# Dev.net
KiCad netlist of a schematic drawn in Altium Designer
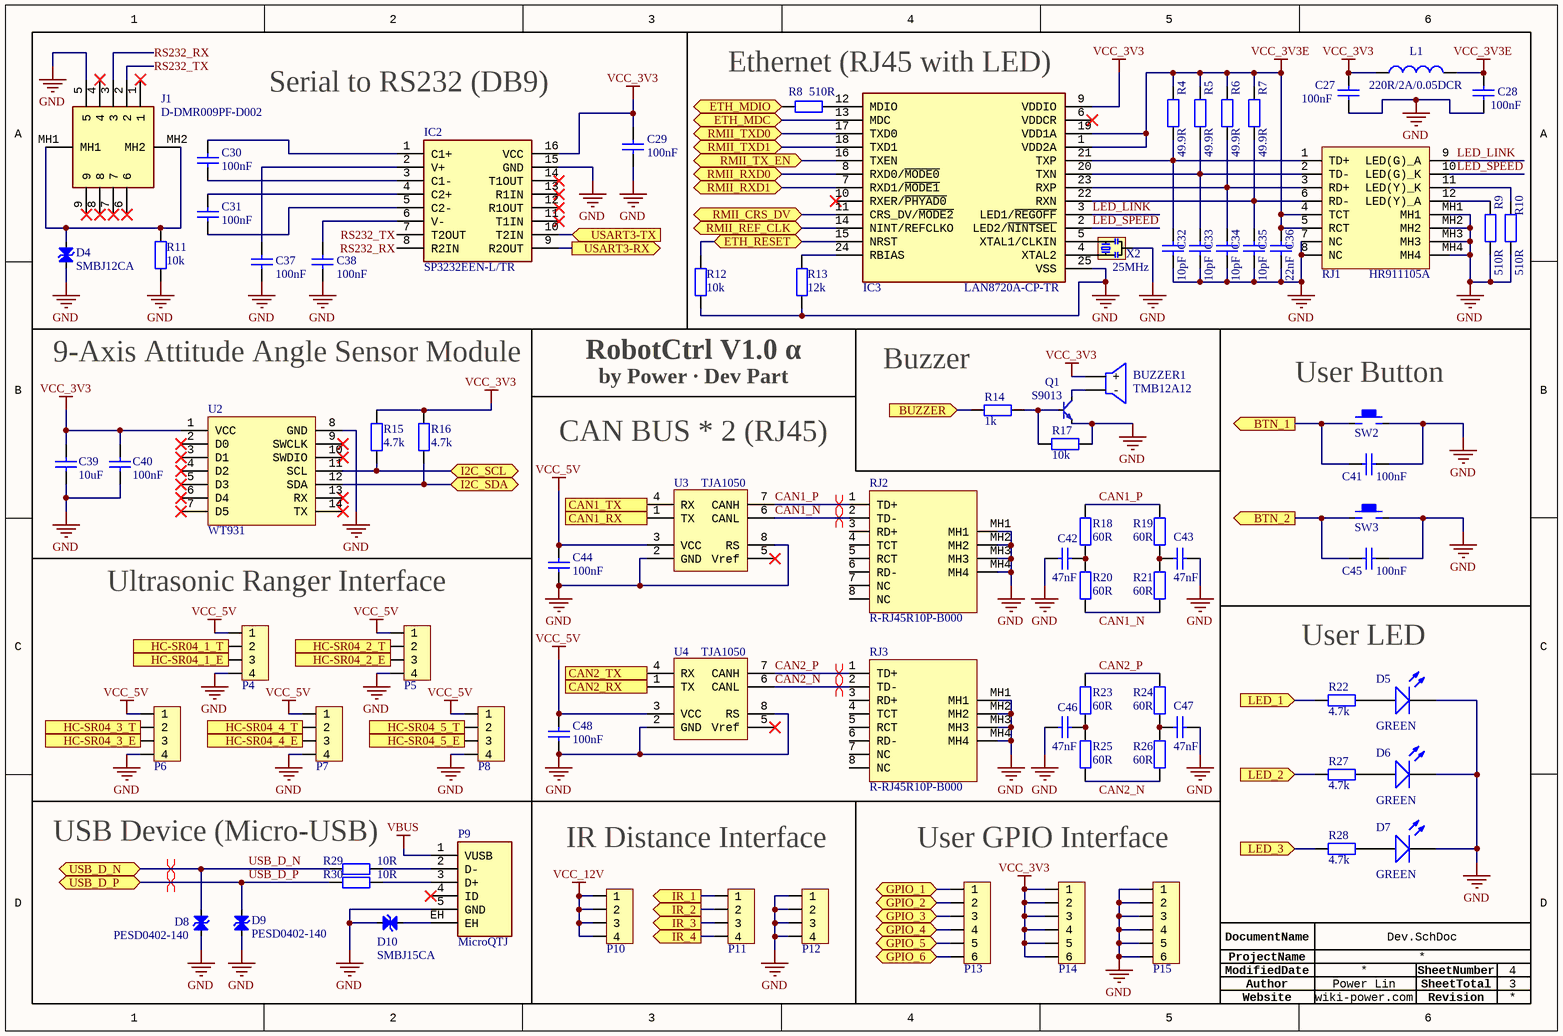
[diagram p0: Dev.SchDoc]

(export (version "E")
  (design (tool "Eeschema 10.0.6"))
  (components
    (comp (ref "BUZZER1")
      (value "TMB12A12")
      (footprint "DIP,P=7.6mm")
      (description "TMB12A12 有源蜂鸣器")
      (libsource (lib "Power_Lib_Altium") (part "BUZZER"))
    )
    (comp (ref "C27")
      (value "100nF")
      (footprint "CAP-0603")
      (description "贴片电容")
      (libsource (lib "Power_Lib_Altium") (part "CAP"))
    )
    (comp (ref "C28")
      (value "100nF")
      (footprint "CAP-0603")
      (description "贴片电容")
      (libsource (lib "Power_Lib_Altium") (part "CAP"))
    )
    (comp (ref "C29")
      (value "100nF")
      (footprint "CAP-0603")
      (description "贴片电容")
      (libsource (lib "Power_Lib_Altium") (part "CAP"))
    )
    (comp (ref "C30")
      (value "100nF")
      (footprint "CAP-0603")
      (description "贴片电容")
      (libsource (lib "Power_Lib_Altium") (part "CAP"))
    )
    (comp (ref "C31")
      (value "100nF")
      (footprint "CAP-0603")
      (description "贴片电容")
      (libsource (lib "Power_Lib_Altium") (part "CAP"))
    )
    (comp (ref "C32")
      (value "10pF")
      (footprint "CAP-0603")
      (description "贴片电容")
      (libsource (lib "Power_Lib_Altium") (part "CAP"))
    )
    (comp (ref "C33")
      (value "10pF")
      (footprint "CAP-0603")
      (description "贴片电容")
      (libsource (lib "Power_Lib_Altium") (part "CAP"))
    )
    (comp (ref "C34")
      (value "10pF")
      (footprint "CAP-0603")
      (description "贴片电容")
      (libsource (lib "Power_Lib_Altium") (part "CAP"))
    )
    (comp (ref "C35")
      (value "10pF")
      (footprint "CAP-0603")
      (description "贴片电容")
      (libsource (lib "Power_Lib_Altium") (part "CAP"))
    )
    (comp (ref "C36")
      (value "22nF")
      (footprint "CAP-0603")
      (description "贴片电容")
      (libsource (lib "Power_Lib_Altium") (part "CAP"))
    )
    (comp (ref "C37")
      (value "100nF")
      (footprint "CAP-0603")
      (description "贴片电容")
      (libsource (lib "Power_Lib_Altium") (part "CAP"))
    )
    (comp (ref "C38")
      (value "100nF")
      (footprint "CAP-0603")
      (description "贴片电容")
      (libsource (lib "Power_Lib_Altium") (part "CAP"))
    )
    (comp (ref "C39")
      (value "10uF")
      (footprint "CAP-0603")
      (description "贴片电容")
      (libsource (lib "Power_Lib_Altium") (part "CAP"))
    )
    (comp (ref "C40")
      (value "100nF")
      (footprint "CAP-0603")
      (description "贴片电容")
      (libsource (lib "Power_Lib_Altium") (part "CAP"))
    )
    (comp (ref "C41")
      (value "100nF")
      (footprint "CAP-0603")
      (description "贴片电容")
      (libsource (lib "Power_Lib_Altium") (part "CAP"))
    )
    (comp (ref "C42")
      (value "47nF")
      (footprint "CAP-0603")
      (description "贴片电容")
      (libsource (lib "Power_Lib_Altium") (part "CAP"))
    )
    (comp (ref "C43")
      (value "47nF")
      (footprint "CAP-0603")
      (description "贴片电容")
      (libsource (lib "Power_Lib_Altium") (part "CAP"))
    )
    (comp (ref "C44")
      (value "100nF")
      (footprint "CAP-0603")
      (description "贴片电容")
      (libsource (lib "Power_Lib_Altium") (part "CAP"))
    )
    (comp (ref "C45")
      (value "100nF")
      (footprint "CAP-0603")
      (description "贴片电容")
      (libsource (lib "Power_Lib_Altium") (part "CAP"))
    )
    (comp (ref "C46")
      (value "47nF")
      (footprint "CAP-0603")
      (description "贴片电容")
      (libsource (lib "Power_Lib_Altium") (part "CAP"))
    )
    (comp (ref "C47")
      (value "47nF")
      (footprint "CAP-0603")
      (description "贴片电容")
      (libsource (lib "Power_Lib_Altium") (part "CAP"))
    )
    (comp (ref "C48")
      (value "100nF")
      (footprint "CAP-0603")
      (description "贴片电容")
      (libsource (lib "Power_Lib_Altium") (part "CAP"))
    )
    (comp (ref "D4")
      (value "SMBJ12CA")
      (footprint "DO-214AA/SMB")
      (libsource (lib "Power_Lib_Altium") (part "TVS_C"))
    )
    (comp (ref "D5")
      (value "GREEN")
      (footprint "LED-0603")
      (description "发光二极管")
      (libsource (lib "Power_Lib_Altium") (part "LED"))
    )
    (comp (ref "D6")
      (value "GREEN")
      (footprint "LED-0603")
      (description "发光二极管")
      (libsource (lib "Power_Lib_Altium") (part "LED"))
    )
    (comp (ref "D7")
      (value "GREEN")
      (footprint "LED-0603")
      (description "发光二极管")
      (libsource (lib "Power_Lib_Altium") (part "LED"))
    )
    (comp (ref "D8")
      (value "PESD0402-140")
      (footprint "D-0402")
      (libsource (lib "Power_Lib_Altium") (part "TVS_C"))
    )
    (comp (ref "D9")
      (value "PESD0402-140")
      (footprint "D-0402")
      (libsource (lib "Power_Lib_Altium") (part "TVS_C"))
    )
    (comp (ref "D10")
      (value "SMBJ15CA")
      (footprint "DO-214AA/SMB")
      (libsource (lib "Power_Lib_Altium") (part "TVS_C"))
    )
    (comp (ref "IC2")
      (value "SP3232EEN-L/TR")
      (footprint "SOIC-16_150mil")
      (description "RS232 芯片")
      (fields (field (name "MOUSER PART NUMBER") "701-SP3232EEN-L/TR"))
      (libsource (lib "Power_Lib_Altium") (part "SP3232EEN"))
    )
    (comp (ref "IC3")
      (value "LAN8720A-CP-TR")
      (footprint "QFN-24-4x4")
      (description "Integrated Circuit")
      (fields (field (name "MOUSER PART NUMBER") "886-LAN8720A-CP-TR"))
      (libsource (lib "Power_Lib_Altium") (part "LAN8720A-CP-TR"))
    )
    (comp (ref "J1")
      (value "D-DMR009PF-D002")
      (footprint "Through Hole,P=2.77mm")
      (description "D-Sub 连接器")
      (fields
        (field (name "MANUFACTURER_PART_NUMBER") "5747844-5")
        (field (name "MOUSER PART NUMBER") "571-5747844-5")
      )
      (libsource (lib "Power_Lib_Altium") (part "DB9"))
    )
    (comp (ref "L1")
      (value "220R/2A/0.05DCR")
      (footprint "L-0603")
      (description "BLM18KG221SN1D")
      (libsource (lib "Power_Lib_Altium") (part "BEAD"))
    )
    (comp (ref "P4")
      (value "HDR1x4_2.54")
      (footprint "HDR1x4_2.54_180")
      (description "Header")
      (libsource (lib "Power_Lib_Altium") (part "HDR1x4_2.54"))
    )
    (comp (ref "P5")
      (value "HDR1x4_2.54")
      (footprint "HDR1x4_2.54_180")
      (description "Header")
      (libsource (lib "Power_Lib_Altium") (part "HDR1x4_2.54"))
    )
    (comp (ref "P6")
      (value "HDR1x4_2.54")
      (footprint "HDR1x4_2.54_180")
      (description "Header")
      (libsource (lib "Power_Lib_Altium") (part "HDR1x4_2.54"))
    )
    (comp (ref "P7")
      (value "HDR1x4_2.54")
      (footprint "HDR1x4_2.54_180")
      (description "Header")
      (libsource (lib "Power_Lib_Altium") (part "HDR1x4_2.54"))
    )
    (comp (ref "P8")
      (value "HDR1x4_2.54")
      (footprint "HDR1x4_2.54_180")
      (description "Header")
      (libsource (lib "Power_Lib_Altium") (part "HDR1x4_2.54"))
    )
    (comp (ref "P9")
      (value "MicroQTJ")
      (footprint "USB-MICRO")
      (description "USB_MICRO")
      (libsource (lib "Power_Lib_Altium") (part "USB_MICRO"))
    )
    (comp (ref "P10")
      (value "HDR1x4_2.54")
      (footprint "HDR1x4_2.54_180")
      (description "Header")
      (libsource (lib "Power_Lib_Altium") (part "HDR1x4_2.54"))
    )
    (comp (ref "P11")
      (value "HDR1x4_2.54")
      (footprint "HDR1x4_2.54_180")
      (description "Header")
      (libsource (lib "Power_Lib_Altium") (part "HDR1x4_2.54"))
    )
    (comp (ref "P12")
      (value "HDR1x4_2.54")
      (footprint "HDR1x4_2.54_180")
      (description "Header")
      (libsource (lib "Power_Lib_Altium") (part "HDR1x4_2.54"))
    )
    (comp (ref "P13")
      (value "HDR1x6")
      (footprint "HDR1X6_2.54_180")
      (description "Header")
      (libsource (lib "Power_Lib_Altium") (part "HDR1x6_2.54"))
    )
    (comp (ref "P14")
      (value "HDR1x6")
      (footprint "HDR1X6_2.54_180")
      (description "Header")
      (libsource (lib "Power_Lib_Altium") (part "HDR1x6_2.54"))
    )
    (comp (ref "P15")
      (value "HDR1x6")
      (footprint "HDR1X6_2.54_180")
      (description "Header")
      (libsource (lib "Power_Lib_Altium") (part "HDR1x6_2.54"))
    )
    (comp (ref "Q1")
      (value "S9013")
      (footprint "SOT-23-3")
      (libsource (lib "Power_Lib_Altium") (part "BJT_NPN"))
    )
    (comp (ref "R4")
      (value "49.9R")
      (footprint "R-0603")
      (description "贴片电阻")
      (libsource (lib "Power_Lib_Altium") (part "RES"))
    )
    (comp (ref "R5")
      (value "49.9R")
      (footprint "R-0603")
      (description "贴片电阻")
      (libsource (lib "Power_Lib_Altium") (part "RES"))
    )
    (comp (ref "R6")
      (value "49.9R")
      (footprint "R-0603")
      (description "贴片电阻")
      (libsource (lib "Power_Lib_Altium") (part "RES"))
    )
    (comp (ref "R7")
      (value "49.9R")
      (footprint "R-0603")
      (description "贴片电阻")
      (libsource (lib "Power_Lib_Altium") (part "RES"))
    )
    (comp (ref "R8")
      (value "510R")
      (footprint "R-0603")
      (description "贴片电阻")
      (libsource (lib "") (part "RES_1"))
    )
    (comp (ref "R9")
      (value "510R")
      (footprint "R-0603")
      (description "贴片电阻")
      (libsource (lib "Power_Lib_Altium") (part "RES"))
    )
    (comp (ref "R10")
      (value "510R")
      (footprint "R-0603")
      (description "贴片电阻")
      (libsource (lib "Power_Lib_Altium") (part "RES"))
    )
    (comp (ref "R11")
      (value "10k")
      (footprint "R-0603")
      (description "贴片电阻")
      (libsource (lib "Power_Lib_Altium") (part "RES"))
    )
    (comp (ref "R12")
      (value "10k")
      (footprint "R-0603")
      (description "贴片电阻")
      (libsource (lib "") (part "RES_3"))
    )
    (comp (ref "R13")
      (value "12k")
      (footprint "R-0603")
      (description "贴片电阻")
      (libsource (lib "") (part "RES_3"))
    )
    (comp (ref "R14")
      (value "1k")
      (footprint "R-0603")
      (description "贴片电阻")
      (libsource (lib "") (part "RES_2"))
    )
    (comp (ref "R15")
      (value "4.7k")
      (footprint "R-0603")
      (description "贴片电阻")
      (libsource (lib "Power_Lib_Altium") (part "RES"))
    )
    (comp (ref "R16")
      (value "4.7k")
      (footprint "R-0603")
      (description "贴片电阻")
      (libsource (lib "Power_Lib_Altium") (part "RES"))
    )
    (comp (ref "R17")
      (value "10k")
      (footprint "R-0603")
      (description "贴片电阻")
      (libsource (lib "") (part "RES_1"))
    )
    (comp (ref "R18")
      (value "60R")
      (footprint "R-0603")
      (description "贴片电阻")
      (libsource (lib "") (part "RES_3"))
    )
    (comp (ref "R19")
      (value "60R")
      (footprint "R-0603")
      (description "贴片电阻")
      (libsource (lib "Power_Lib_Altium") (part "RES"))
    )
    (comp (ref "R20")
      (value "60R")
      (footprint "R-0603")
      (description "贴片电阻")
      (libsource (lib "") (part "RES_3"))
    )
    (comp (ref "R21")
      (value "60R")
      (footprint "R-0603")
      (description "贴片电阻")
      (libsource (lib "Power_Lib_Altium") (part "RES"))
    )
    (comp (ref "R22")
      (value "4.7k")
      (footprint "R-0603")
      (description "贴片电阻")
      (libsource (lib "") (part "RES_1"))
    )
    (comp (ref "R23")
      (value "60R")
      (footprint "R-0603")
      (description "贴片电阻")
      (libsource (lib "") (part "RES_3"))
    )
    (comp (ref "R24")
      (value "60R")
      (footprint "R-0603")
      (description "贴片电阻")
      (libsource (lib "Power_Lib_Altium") (part "RES"))
    )
    (comp (ref "R25")
      (value "60R")
      (footprint "R-0603")
      (description "贴片电阻")
      (libsource (lib "") (part "RES_3"))
    )
    (comp (ref "R26")
      (value "60R")
      (footprint "R-0603")
      (description "贴片电阻")
      (libsource (lib "Power_Lib_Altium") (part "RES"))
    )
    (comp (ref "R27")
      (value "4.7k")
      (footprint "R-0603")
      (description "贴片电阻")
      (libsource (lib "") (part "RES_1"))
    )
    (comp (ref "R28")
      (value "4.7k")
      (footprint "R-0603")
      (description "贴片电阻")
      (libsource (lib "") (part "RES_1"))
    )
    (comp (ref "R29")
      (value "10R")
      (footprint "R-0603")
      (description "贴片电阻")
      (libsource (lib "") (part "RES_2"))
    )
    (comp (ref "R30")
      (value "10R")
      (footprint "R-0603")
      (description "贴片电阻")
      (libsource (lib "") (part "RES_2"))
    )
    (comp (ref "RJ1")
      (value "HR911105A")
      (footprint "HR911105A")
      (libsource (lib "Power_Lib_Altium") (part "RJ45_LED"))
    )
    (comp (ref "RJ2")
      (value "R-RJ45R10P-B000")
      (footprint "RRJ45R10PB000")
      (libsource (lib "Power_Lib_Altium") (part "RJ45"))
    )
    (comp (ref "RJ3")
      (value "R-RJ45R10P-B000")
      (footprint "RRJ45R10PB000")
      (libsource (lib "Power_Lib_Altium") (part "RJ45"))
    )
    (comp (ref "SW2")
      (value "KEY")
      (footprint "KEY-4P-4.2*3.4*2.5")
      (description "按键开关")
      (libsource (lib "Power_Lib_Altium") (part "KEY"))
    )
    (comp (ref "SW3")
      (value "KEY")
      (footprint "KEY-4P-4.2*3.4*2.5")
      (description "按键开关")
      (libsource (lib "Power_Lib_Altium") (part "KEY"))
    )
    (comp (ref "U2")
      (value "WT931")
      (footprint "WT931")
      (description "陀螺仪模组")
      (libsource (lib "Power_Lib_Altium") (part "WT931"))
    )
    (comp (ref "U3")
      (value "TJA1050")
      (footprint "SOIC_8")
      (description "CAN 控制器（5V）")
      (libsource (lib "Power_Lib_Altium") (part "TJA1050"))
    )
    (comp (ref "U4")
      (value "TJA1050")
      (footprint "SOIC_8")
      (description "CAN 控制器（5V）")
      (libsource (lib "Power_Lib_Altium") (part "TJA1050"))
    )
    (comp (ref "X2")
      (value "25MHz")
      (footprint "SMD3213-3P")
      (description "CSTCE25M00G51-R0")
      (libsource (lib "Power_Lib_Altium") (part "XTAL"))
    )
  )
  (nets
    (net (code "1") (name "/BTN_1") (class "Default")
      (node (ref "C41") (pin "2") (pinfunction "2_2") (pintype "passive"))
      (node (ref "SW2") (pin "1") (pinfunction "1_1") (pintype "passive"))
    )
    (net (code "2") (name "/BTN_2") (class "Default")
      (node (ref "C45") (pin "2") (pinfunction "2_2") (pintype "passive"))
      (node (ref "SW3") (pin "1") (pinfunction "1_1") (pintype "passive"))
    )
    (net (code "3") (name "/BUZZER") (class "Default")
      (node (ref "R14") (pin "1") (pinfunction "1_1") (pintype "passive"))
    )
    (net (code "4") (name "/CAN1_N") (class "Default")
      (node (ref "R20") (pin "2") (pinfunction "2_2") (pintype "passive"))
      (node (ref "R21") (pin "1") (pinfunction "1_1") (pintype "passive"))
      (node (ref "RJ2") (pin "2") (pinfunction "TD-_2") (pintype "passive"))
      (node (ref "U3") (pin "6") (pinfunction "CANL_6") (pintype "passive"))
    )
    (net (code "5") (name "/CAN1_P") (class "Default")
      (node (ref "R18") (pin "1") (pinfunction "1_1") (pintype "passive"))
      (node (ref "R19") (pin "2") (pinfunction "2_2") (pintype "passive"))
      (node (ref "RJ2") (pin "1") (pinfunction "TD+_1") (pintype "passive"))
      (node (ref "U3") (pin "7") (pinfunction "CANH_7") (pintype "passive"))
    )
    (net (code "6") (name "/CAN1_RX") (class "Default")
      (node (ref "U3") (pin "1") (pinfunction "TX_1") (pintype "passive"))
    )
    (net (code "7") (name "/CAN1_TX") (class "Default")
      (node (ref "U3") (pin "4") (pinfunction "RX_4") (pintype "passive"))
    )
    (net (code "8") (name "/CAN2_N") (class "Default")
      (node (ref "R25") (pin "2") (pinfunction "2_2") (pintype "passive"))
      (node (ref "R26") (pin "1") (pinfunction "1_1") (pintype "passive"))
      (node (ref "RJ3") (pin "2") (pinfunction "TD-_2") (pintype "passive"))
      (node (ref "U4") (pin "6") (pinfunction "CANL_6") (pintype "passive"))
    )
    (net (code "9") (name "/CAN2_P") (class "Default")
      (node (ref "R23") (pin "1") (pinfunction "1_1") (pintype "passive"))
      (node (ref "R24") (pin "2") (pinfunction "2_2") (pintype "passive"))
      (node (ref "RJ3") (pin "1") (pinfunction "TD+_1") (pintype "passive"))
      (node (ref "U4") (pin "7") (pinfunction "CANH_7") (pintype "passive"))
    )
    (net (code "10") (name "/CAN2_RX") (class "Default")
      (node (ref "U4") (pin "1") (pinfunction "TX_1") (pintype "passive"))
    )
    (net (code "11") (name "/CAN2_TX") (class "Default")
      (node (ref "U4") (pin "4") (pinfunction "RX_4") (pintype "passive"))
    )
    (net (code "12") (name "/ETH_MDC") (class "Default")
      (node (ref "IC3") (pin "13") (pinfunction "MDC_13") (pintype "passive"))
    )
    (net (code "13") (name "/ETH_MDIO") (class "Default")
      (node (ref "R8") (pin "2") (pinfunction "2_2") (pintype "passive"))
    )
    (net (code "14") (name "/ETH_RESET") (class "Default")
      (node (ref "IC3") (pin "15") (pinfunction "NRST_15") (pintype "passive"))
      (node (ref "R12") (pin "1") (pinfunction "1_1") (pintype "passive"))
    )
    (net (code "15") (name "/GPIO_1") (class "Default")
      (node (ref "P13") (pin "1") (pinfunction "1_1") (pintype "passive"))
    )
    (net (code "16") (name "/GPIO_2") (class "Default")
      (node (ref "P13") (pin "2") (pinfunction "2_2") (pintype "passive"))
    )
    (net (code "17") (name "/GPIO_3") (class "Default")
      (node (ref "P13") (pin "3") (pinfunction "3_3") (pintype "passive"))
    )
    (net (code "18") (name "/GPIO_4") (class "Default")
      (node (ref "P13") (pin "4") (pinfunction "4_4") (pintype "passive"))
    )
    (net (code "19") (name "/GPIO_5") (class "Default")
      (node (ref "P13") (pin "5") (pinfunction "5_5") (pintype "passive"))
    )
    (net (code "20") (name "/GPIO_6") (class "Default")
      (node (ref "P13") (pin "6") (pinfunction "6_6") (pintype "passive"))
    )
    (net (code "21") (name "/HC-SR04_1_E") (class "Default")
      (node (ref "P4") (pin "3") (pinfunction "3_3") (pintype "passive"))
    )
    (net (code "22") (name "/HC-SR04_1_T") (class "Default")
      (node (ref "P4") (pin "2") (pinfunction "2_2") (pintype "passive"))
    )
    (net (code "23") (name "/HC-SR04_2_E") (class "Default")
      (node (ref "P5") (pin "3") (pinfunction "3_3") (pintype "passive"))
    )
    (net (code "24") (name "/HC-SR04_2_T") (class "Default")
      (node (ref "P5") (pin "2") (pinfunction "2_2") (pintype "passive"))
    )
    (net (code "25") (name "/HC-SR04_3_E") (class "Default")
      (node (ref "P6") (pin "3") (pinfunction "3_3") (pintype "passive"))
    )
    (net (code "26") (name "/HC-SR04_3_T") (class "Default")
      (node (ref "P6") (pin "2") (pinfunction "2_2") (pintype "passive"))
    )
    (net (code "27") (name "/HC-SR04_4_E") (class "Default")
      (node (ref "P7") (pin "3") (pinfunction "3_3") (pintype "passive"))
    )
    (net (code "28") (name "/HC-SR04_4_T") (class "Default")
      (node (ref "P7") (pin "2") (pinfunction "2_2") (pintype "passive"))
    )
    (net (code "29") (name "/HC-SR04_5_E") (class "Default")
      (node (ref "P8") (pin "3") (pinfunction "3_3") (pintype "passive"))
    )
    (net (code "30") (name "/HC-SR04_5_T") (class "Default")
      (node (ref "P8") (pin "2") (pinfunction "2_2") (pintype "passive"))
    )
    (net (code "31") (name "/I2C_SCL") (class "Default")
      (node (ref "R15") (pin "1") (pinfunction "1_1") (pintype "passive"))
      (node (ref "U2") (pin "11") (pinfunction "SCL_11") (pintype "passive"))
    )
    (net (code "32") (name "/I2C_SDA") (class "Default")
      (node (ref "R16") (pin "1") (pinfunction "1_1") (pintype "passive"))
      (node (ref "U2") (pin "12") (pinfunction "SDA_12") (pintype "passive"))
    )
    (net (code "33") (name "/IR_1") (class "Default")
      (node (ref "P11") (pin "1") (pinfunction "1_1") (pintype "passive"))
    )
    (net (code "34") (name "/IR_2") (class "Default")
      (node (ref "P11") (pin "2") (pinfunction "2_2") (pintype "passive"))
    )
    (net (code "35") (name "/IR_3") (class "Default")
      (node (ref "P11") (pin "3") (pinfunction "3_3") (pintype "passive"))
    )
    (net (code "36") (name "/IR_4") (class "Default")
      (node (ref "P11") (pin "4") (pinfunction "4_4") (pintype "passive"))
    )
    (net (code "37") (name "/LED_1") (class "Default")
      (node (ref "R22") (pin "2") (pinfunction "2_2") (pintype "passive"))
    )
    (net (code "38") (name "/LED_2") (class "Default")
      (node (ref "R27") (pin "2") (pinfunction "2_2") (pintype "passive"))
    )
    (net (code "39") (name "/LED_3") (class "Default")
      (node (ref "R28") (pin "2") (pinfunction "2_2") (pintype "passive"))
    )
    (net (code "40") (name "/LED_LINK") (class "Default")
      (node (ref "IC3") (pin "3") (pinfunction "LED1/~{REGOFF}_3") (pintype "passive"))
      (node (ref "RJ1") (pin "9") (pinfunction "LED(G)_A_9") (pintype "passive"))
    )
    (net (code "41") (name "/LED_SPEED") (class "Default")
      (node (ref "IC3") (pin "2") (pinfunction "LED2/~{NINTSEL}_2") (pintype "passive"))
      (node (ref "RJ1") (pin "10") (pinfunction "LED(G)_K_10") (pintype "passive"))
    )
    (net (code "42") (name "/RMII_CRS_DV") (class "Default")
      (node (ref "IC3") (pin "11") (pinfunction "CRS_DV/~{MODE2}_11") (pintype "passive"))
    )
    (net (code "43") (name "/RMII_REF_CLK") (class "Default")
      (node (ref "IC3") (pin "14") (pinfunction "NINT/REFCLKO_14") (pintype "passive"))
    )
    (net (code "44") (name "/RMII_RXD0") (class "Default")
      (node (ref "IC3") (pin "8") (pinfunction "RXD0/~{MODE0}_8") (pintype "passive"))
    )
    (net (code "45") (name "/RMII_RXD1") (class "Default")
      (node (ref "IC3") (pin "7") (pinfunction "RXD1/~{MODE1}_7") (pintype "passive"))
    )
    (net (code "46") (name "/RMII_TXD0") (class "Default")
      (node (ref "IC3") (pin "17") (pinfunction "TXD0_17") (pintype "passive"))
    )
    (net (code "47") (name "/RMII_TXD1") (class "Default")
      (node (ref "IC3") (pin "18") (pinfunction "TXD1_18") (pintype "passive"))
    )
    (net (code "48") (name "/RMII_TX_EN") (class "Default")
      (node (ref "IC3") (pin "16") (pinfunction "TXEN_16") (pintype "passive"))
    )
    (net (code "49") (name "/RS232_RX") (class "Default")
      (node (ref "IC2") (pin "8") (pinfunction "R2IN_8") (pintype "passive"))
      (node (ref "J1") (pin "3") (pinfunction "3_3") (pintype "passive"))
    )
    (net (code "50") (name "/RS232_TX") (class "Default")
      (node (ref "IC2") (pin "7") (pinfunction "T2OUT_7") (pintype "passive"))
      (node (ref "J1") (pin "2") (pinfunction "2_2") (pintype "passive"))
    )
    (net (code "51") (name "/USART3-RX") (class "Default")
      (node (ref "IC2") (pin "9") (pinfunction "R2OUT_9") (pintype "passive"))
    )
    (net (code "52") (name "/USART3-TX") (class "Default")
      (node (ref "IC2") (pin "10") (pinfunction "T2IN_10") (pintype "passive"))
    )
    (net (code "53") (name "/USB_D_N") (class "Default")
      (node (ref "D8") (pin "2") (pinfunction "2_2") (pintype "passive"))
      (node (ref "R29") (pin "1") (pinfunction "1_1") (pintype "passive"))
    )
    (net (code "54") (name "/USB_D_P") (class "Default")
      (node (ref "D9") (pin "2") (pinfunction "2_2") (pintype "passive"))
      (node (ref "R30") (pin "1") (pinfunction "1_1") (pintype "passive"))
    )
    (net (code "55") (name "GND") (class "Default")
      (node (ref "C27") (pin "1") (pinfunction "1_1") (pintype "passive"))
      (node (ref "C28") (pin "1") (pinfunction "1_1") (pintype "passive"))
      (node (ref "C29") (pin "1") (pinfunction "1_1") (pintype "passive"))
      (node (ref "C32") (pin "1") (pinfunction "1_1") (pintype "passive"))
      (node (ref "C33") (pin "1") (pinfunction "1_1") (pintype "passive"))
      (node (ref "C34") (pin "1") (pinfunction "1_1") (pintype "passive"))
      (node (ref "C35") (pin "1") (pinfunction "1_1") (pintype "passive"))
      (node (ref "C36") (pin "1") (pinfunction "1_1") (pintype "passive"))
      (node (ref "C37") (pin "1") (pinfunction "1_1") (pintype "passive"))
      (node (ref "C38") (pin "1") (pinfunction "1_1") (pintype "passive"))
      (node (ref "C39") (pin "2") (pinfunction "2_2") (pintype "passive"))
      (node (ref "C40") (pin "2") (pinfunction "2_2") (pintype "passive"))
      (node (ref "C41") (pin "1") (pinfunction "1_1") (pintype "passive"))
      (node (ref "C42") (pin "2") (pinfunction "2_2") (pintype "passive"))
      (node (ref "C43") (pin "2") (pinfunction "2_2") (pintype "passive"))
      (node (ref "C44") (pin "1") (pinfunction "1_1") (pintype "passive"))
      (node (ref "C45") (pin "1") (pinfunction "1_1") (pintype "passive"))
      (node (ref "C46") (pin "2") (pinfunction "2_2") (pintype "passive"))
      (node (ref "C47") (pin "2") (pinfunction "2_2") (pintype "passive"))
      (node (ref "C48") (pin "1") (pinfunction "1_1") (pintype "passive"))
      (node (ref "D10") (pin "2") (pinfunction "2_2") (pintype "passive"))
      (node (ref "D4") (pin "1") (pinfunction "1_1") (pintype "passive"))
      (node (ref "D5") (pin "K") (pinfunction "K_K") (pintype "passive"))
      (node (ref "D6") (pin "K") (pinfunction "K_K") (pintype "passive"))
      (node (ref "D7") (pin "K") (pinfunction "K_K") (pintype "passive"))
      (node (ref "D8") (pin "1") (pinfunction "1_1") (pintype "passive"))
      (node (ref "D9") (pin "1") (pinfunction "1_1") (pintype "passive"))
      (node (ref "IC2") (pin "15") (pinfunction "GND_15") (pintype "passive"))
      (node (ref "IC3") (pin "25") (pinfunction "VSS_25") (pintype "passive"))
      (node (ref "J1") (pin "5") (pinfunction "5_5") (pintype "passive"))
      (node (ref "P12") (pin "1") (pinfunction "1_1") (pintype "passive"))
      (node (ref "P12") (pin "2") (pinfunction "2_2") (pintype "passive"))
      (node (ref "P12") (pin "3") (pinfunction "3_3") (pintype "passive"))
      (node (ref "P12") (pin "4") (pinfunction "4_4") (pintype "passive"))
      (node (ref "P15") (pin "1") (pinfunction "1_1") (pintype "passive"))
      (node (ref "P15") (pin "2") (pinfunction "2_2") (pintype "passive"))
      (node (ref "P15") (pin "3") (pinfunction "3_3") (pintype "passive"))
      (node (ref "P15") (pin "4") (pinfunction "4_4") (pintype "passive"))
      (node (ref "P15") (pin "5") (pinfunction "5_5") (pintype "passive"))
      (node (ref "P15") (pin "6") (pinfunction "6_6") (pintype "passive"))
      (node (ref "P4") (pin "4") (pinfunction "4_4") (pintype "passive"))
      (node (ref "P5") (pin "4") (pinfunction "4_4") (pintype "passive"))
      (node (ref "P6") (pin "4") (pinfunction "4_4") (pintype "passive"))
      (node (ref "P7") (pin "4") (pinfunction "4_4") (pintype "passive"))
      (node (ref "P8") (pin "4") (pinfunction "4_4") (pintype "passive"))
      (node (ref "P9") (pin "5") (pinfunction "GND_5") (pintype "passive"))
      (node (ref "Q1") (pin "2") (pinfunction "E_2") (pintype "passive"))
      (node (ref "R10") (pin "1") (pinfunction "1_1") (pintype "passive"))
      (node (ref "R11") (pin "1") (pinfunction "1_1") (pintype "passive"))
      (node (ref "R12") (pin "2") (pinfunction "2_2") (pintype "passive"))
      (node (ref "R13") (pin "2") (pinfunction "2_2") (pintype "passive"))
      (node (ref "R17") (pin "1") (pinfunction "1_1") (pintype "passive"))
      (node (ref "R9") (pin "1") (pinfunction "1_1") (pintype "passive"))
      (node (ref "RJ1") (pin "7") (pinfunction "NC_7") (pintype "passive"))
      (node (ref "RJ1") (pin "8") (pinfunction "NC_8") (pintype "passive"))
      (node (ref "RJ1") (pin "MH1") (pinfunction "MH1_MH1") (pintype "passive"))
      (node (ref "RJ1") (pin "MH2") (pinfunction "MH2_MH2") (pintype "passive"))
      (node (ref "RJ1") (pin "MH3") (pinfunction "MH3_MH3") (pintype "passive"))
      (node (ref "RJ1") (pin "MH4") (pinfunction "MH4_MH4") (pintype "passive"))
      (node (ref "RJ2") (pin "MH1") (pinfunction "MH1_MH1") (pintype "passive"))
      (node (ref "RJ2") (pin "MH2") (pinfunction "MH2_MH2") (pintype "passive"))
      (node (ref "RJ2") (pin "MH3") (pinfunction "MH3_MH3") (pintype "passive"))
      (node (ref "RJ2") (pin "MH4") (pinfunction "MH4_MH4") (pintype "passive"))
      (node (ref "RJ3") (pin "MH1") (pinfunction "MH1_MH1") (pintype "passive"))
      (node (ref "RJ3") (pin "MH2") (pinfunction "MH2_MH2") (pintype "passive"))
      (node (ref "RJ3") (pin "MH3") (pinfunction "MH3_MH3") (pintype "passive"))
      (node (ref "RJ3") (pin "MH4") (pinfunction "MH4_MH4") (pintype "passive"))
      (node (ref "SW2") (pin "2") (pinfunction "2_2") (pintype "passive"))
      (node (ref "SW3") (pin "2") (pinfunction "2_2") (pintype "passive"))
      (node (ref "U2") (pin "8") (pinfunction "GND_8") (pintype "passive"))
      (node (ref "U3") (pin "2") (pinfunction "GND_2") (pintype "passive"))
      (node (ref "U3") (pin "8") (pinfunction "RS_8") (pintype "passive"))
      (node (ref "U4") (pin "2") (pinfunction "GND_2") (pintype "passive"))
      (node (ref "U4") (pin "8") (pinfunction "RS_8") (pintype "passive"))
      (node (ref "X2") (pin "2") (pinfunction "GND_2") (pintype "passive"))
    )
    (net (code "56") (name "Net-(BUZZER1--)") (class "Default")
      (node (ref "BUZZER1") (pin "2") (pinfunction "-_2") (pintype "passive"))
      (node (ref "Q1") (pin "3") (pinfunction "C_3") (pintype "passive"))
    )
    (net (code "57") (name "Net-(C42-Pad1)") (class "Default")
      (node (ref "C42") (pin "1") (pinfunction "1_1") (pintype "passive"))
      (node (ref "R18") (pin "2") (pinfunction "2_2") (pintype "passive"))
      (node (ref "R20") (pin "1") (pinfunction "1_1") (pintype "passive"))
    )
    (net (code "58") (name "Net-(C43-Pad1)") (class "Default")
      (node (ref "C43") (pin "1") (pinfunction "1_1") (pintype "passive"))
      (node (ref "R19") (pin "1") (pinfunction "1_1") (pintype "passive"))
      (node (ref "R21") (pin "2") (pinfunction "2_2") (pintype "passive"))
    )
    (net (code "59") (name "Net-(C46-Pad1)") (class "Default")
      (node (ref "C46") (pin "1") (pinfunction "1_1") (pintype "passive"))
      (node (ref "R23") (pin "2") (pinfunction "2_2") (pintype "passive"))
      (node (ref "R25") (pin "1") (pinfunction "1_1") (pintype "passive"))
    )
    (net (code "60") (name "Net-(C47-Pad1)") (class "Default")
      (node (ref "C47") (pin "1") (pinfunction "1_1") (pintype "passive"))
      (node (ref "R24") (pin "1") (pinfunction "1_1") (pintype "passive"))
      (node (ref "R26") (pin "2") (pinfunction "2_2") (pintype "passive"))
    )
    (net (code "61") (name "Net-(D4-Pad2)") (class "Default")
      (node (ref "D4") (pin "2") (pinfunction "2_2") (pintype "passive"))
      (node (ref "J1") (pin "MH1") (pinfunction "MH1_MH1") (pintype "passive"))
      (node (ref "J1") (pin "MH2") (pinfunction "MH2_MH2") (pintype "passive"))
      (node (ref "R11") (pin "2") (pinfunction "2_2") (pintype "passive"))
    )
    (net (code "62") (name "Net-(D5-PadA)") (class "Default")
      (node (ref "D5") (pin "A") (pinfunction "A_A") (pintype "passive"))
      (node (ref "R22") (pin "1") (pinfunction "1_1") (pintype "passive"))
    )
    (net (code "63") (name "Net-(D6-PadA)") (class "Default")
      (node (ref "D6") (pin "A") (pinfunction "A_A") (pintype "passive"))
      (node (ref "R27") (pin "1") (pinfunction "1_1") (pintype "passive"))
    )
    (net (code "64") (name "Net-(D7-PadA)") (class "Default")
      (node (ref "D7") (pin "A") (pinfunction "A_A") (pintype "passive"))
      (node (ref "R28") (pin "1") (pinfunction "1_1") (pintype "passive"))
    )
    (net (code "65") (name "Net-(D10-Pad1)") (class "Default")
      (node (ref "D10") (pin "1") (pinfunction "1_1") (pintype "passive"))
      (node (ref "P9") (pin "EH") (pinfunction "EH_EH") (pintype "passive"))
    )
    (net (code "66") (name "Net-(IC2-C1+)") (class "Default")
      (node (ref "C30") (pin "2") (pinfunction "2_2") (pintype "passive"))
      (node (ref "IC2") (pin "1") (pinfunction "C1+_1") (pintype "passive"))
    )
    (net (code "67") (name "Net-(IC2-C1-)") (class "Default")
      (node (ref "C30") (pin "1") (pinfunction "1_1") (pintype "passive"))
      (node (ref "IC2") (pin "3") (pinfunction "C1-_3") (pintype "passive"))
    )
    (net (code "68") (name "Net-(IC2-C2+)") (class "Default")
      (node (ref "C31") (pin "2") (pinfunction "2_2") (pintype "passive"))
      (node (ref "IC2") (pin "4") (pinfunction "C2+_4") (pintype "passive"))
    )
    (net (code "69") (name "Net-(IC2-C2-)") (class "Default")
      (node (ref "C31") (pin "1") (pinfunction "1_1") (pintype "passive"))
      (node (ref "IC2") (pin "5") (pinfunction "C2-_5") (pintype "passive"))
    )
    (net (code "70") (name "Net-(IC2-V+)") (class "Default")
      (node (ref "C37") (pin "2") (pinfunction "2_2") (pintype "passive"))
      (node (ref "IC2") (pin "2") (pinfunction "V+_2") (pintype "passive"))
    )
    (net (code "71") (name "Net-(IC2-V-)") (class "Default")
      (node (ref "C38") (pin "2") (pinfunction "2_2") (pintype "passive"))
      (node (ref "IC2") (pin "6") (pinfunction "V-_6") (pintype "passive"))
    )
    (net (code "72") (name "Net-(IC3-MDIO)") (class "Default")
      (node (ref "IC3") (pin "12") (pinfunction "MDIO_12") (pintype "passive"))
      (node (ref "R8") (pin "1") (pinfunction "1_1") (pintype "passive"))
    )
    (net (code "73") (name "Net-(IC3-RBIAS)") (class "Default")
      (node (ref "IC3") (pin "24") (pinfunction "RBIAS_24") (pintype "passive"))
      (node (ref "R13") (pin "1") (pinfunction "1_1") (pintype "passive"))
    )
    (net (code "74") (name "Net-(IC3-RXN)") (class "Default")
      (node (ref "C35") (pin "2") (pinfunction "2_2") (pintype "passive"))
      (node (ref "IC3") (pin "22") (pinfunction "RXN_22") (pintype "passive"))
      (node (ref "R7") (pin "1") (pinfunction "1_1") (pintype "passive"))
      (node (ref "RJ1") (pin "6") (pinfunction "RD-_6") (pintype "passive"))
    )
    (net (code "75") (name "Net-(IC3-RXP)") (class "Default")
      (node (ref "C34") (pin "2") (pinfunction "2_2") (pintype "passive"))
      (node (ref "IC3") (pin "23") (pinfunction "RXP_23") (pintype "passive"))
      (node (ref "R6") (pin "1") (pinfunction "1_1") (pintype "passive"))
      (node (ref "RJ1") (pin "3") (pinfunction "RD+_3") (pintype "passive"))
    )
    (net (code "76") (name "Net-(IC3-TXN)") (class "Default")
      (node (ref "C33") (pin "2") (pinfunction "2_2") (pintype "passive"))
      (node (ref "IC3") (pin "20") (pinfunction "TXN_20") (pintype "passive"))
      (node (ref "R5") (pin "1") (pinfunction "1_1") (pintype "passive"))
      (node (ref "RJ1") (pin "2") (pinfunction "TD-_2") (pintype "passive"))
    )
    (net (code "77") (name "Net-(IC3-TXP)") (class "Default")
      (node (ref "C32") (pin "2") (pinfunction "2_2") (pintype "passive"))
      (node (ref "IC3") (pin "21") (pinfunction "TXP_21") (pintype "passive"))
      (node (ref "R4") (pin "1") (pinfunction "1_1") (pintype "passive"))
      (node (ref "RJ1") (pin "1") (pinfunction "TD+_1") (pintype "passive"))
    )
    (net (code "78") (name "Net-(IC3-XTAL1{slash}CLKIN)") (class "Default")
      (node (ref "IC3") (pin "5") (pinfunction "XTAL1/CLKIN_5") (pintype "passive"))
      (node (ref "X2") (pin "3") (pinfunction "OSC2_3") (pintype "passive"))
    )
    (net (code "79") (name "Net-(IC3-XTAL2)") (class "Default")
      (node (ref "IC3") (pin "4") (pinfunction "XTAL2_4") (pintype "passive"))
      (node (ref "X2") (pin "1") (pinfunction "OSC1_1") (pintype "passive"))
    )
    (net (code "80") (name "Net-(P9-D+)") (class "Default")
      (node (ref "P9") (pin "3") (pinfunction "D+_3") (pintype "passive"))
      (node (ref "R30") (pin "2") (pinfunction "2_2") (pintype "passive"))
    )
    (net (code "81") (name "Net-(P9-D-)") (class "Default")
      (node (ref "P9") (pin "2") (pinfunction "D-_2") (pintype "passive"))
      (node (ref "R29") (pin "2") (pinfunction "2_2") (pintype "passive"))
    )
    (net (code "82") (name "Net-(Q1-B)") (class "Default")
      (node (ref "Q1") (pin "1") (pinfunction "B_1") (pintype "passive"))
      (node (ref "R14") (pin "2") (pinfunction "2_2") (pintype "passive"))
      (node (ref "R17") (pin "2") (pinfunction "2_2") (pintype "passive"))
    )
    (net (code "83") (name "Net-(RJ1-LED(Y)_A)") (class "Default")
      (node (ref "R9") (pin "2") (pinfunction "2_2") (pintype "passive"))
      (node (ref "RJ1") (pin "12") (pinfunction "LED(Y)_A_12") (pintype "passive"))
    )
    (net (code "84") (name "Net-(RJ1-LED(Y)_K)") (class "Default")
      (node (ref "R10") (pin "2") (pinfunction "2_2") (pintype "passive"))
      (node (ref "RJ1") (pin "11") (pinfunction "LED(Y)_K_11") (pintype "passive"))
    )
    (net (code "85") (name "VBUS") (class "Default")
      (node (ref "P9") (pin "1") (pinfunction "VUSB_1") (pintype "passive"))
    )
    (net (code "86") (name "VCC_3V3") (class "Default")
      (node (ref "BUZZER1") (pin "1") (pinfunction "+_1") (pintype "passive"))
      (node (ref "C27") (pin "2") (pinfunction "2_2") (pintype "passive"))
      (node (ref "C29") (pin "2") (pinfunction "2_2") (pintype "passive"))
      (node (ref "C39") (pin "1") (pinfunction "1_1") (pintype "passive"))
      (node (ref "C40") (pin "1") (pinfunction "1_1") (pintype "passive"))
      (node (ref "IC2") (pin "16") (pinfunction "VCC_16") (pintype "passive"))
      (node (ref "IC3") (pin "9") (pinfunction "VDDIO_9") (pintype "passive"))
      (node (ref "L1") (pin "1") (pinfunction "1_1") (pintype "passive"))
      (node (ref "P14") (pin "1") (pinfunction "1_1") (pintype "passive"))
      (node (ref "P14") (pin "2") (pinfunction "2_2") (pintype "passive"))
      (node (ref "P14") (pin "3") (pinfunction "3_3") (pintype "passive"))
      (node (ref "P14") (pin "4") (pinfunction "4_4") (pintype "passive"))
      (node (ref "P14") (pin "5") (pinfunction "5_5") (pintype "passive"))
      (node (ref "P14") (pin "6") (pinfunction "6_6") (pintype "passive"))
      (node (ref "R15") (pin "2") (pinfunction "2_2") (pintype "passive"))
      (node (ref "R16") (pin "2") (pinfunction "2_2") (pintype "passive"))
      (node (ref "U2") (pin "1") (pinfunction "VCC_1") (pintype "passive"))
    )
    (net (code "87") (name "VCC_3V3E") (class "Default")
      (node (ref "C28") (pin "2") (pinfunction "2_2") (pintype "passive"))
      (node (ref "C36") (pin "2") (pinfunction "2_2") (pintype "passive"))
      (node (ref "IC3") (pin "1") (pinfunction "VDD2A_1") (pintype "passive"))
      (node (ref "IC3") (pin "19") (pinfunction "VDD1A_19") (pintype "passive"))
      (node (ref "L1") (pin "2") (pinfunction "2_2") (pintype "passive"))
      (node (ref "R4") (pin "2") (pinfunction "2_2") (pintype "passive"))
      (node (ref "R5") (pin "2") (pinfunction "2_2") (pintype "passive"))
      (node (ref "R6") (pin "2") (pinfunction "2_2") (pintype "passive"))
      (node (ref "R7") (pin "2") (pinfunction "2_2") (pintype "passive"))
      (node (ref "RJ1") (pin "4") (pinfunction "TCT_4") (pintype "passive"))
      (node (ref "RJ1") (pin "5") (pinfunction "RCT_5") (pintype "passive"))
    )
    (net (code "88") (name "VCC_5V") (class "Default")
      (node (ref "C44") (pin "2") (pinfunction "2_2") (pintype "passive"))
      (node (ref "C48") (pin "2") (pinfunction "2_2") (pintype "passive"))
      (node (ref "P4") (pin "1") (pinfunction "1_1") (pintype "passive"))
      (node (ref "P5") (pin "1") (pinfunction "1_1") (pintype "passive"))
      (node (ref "P6") (pin "1") (pinfunction "1_1") (pintype "passive"))
      (node (ref "P7") (pin "1") (pinfunction "1_1") (pintype "passive"))
      (node (ref "P8") (pin "1") (pinfunction "1_1") (pintype "passive"))
      (node (ref "U3") (pin "3") (pinfunction "VCC_3") (pintype "passive"))
      (node (ref "U4") (pin "3") (pinfunction "VCC_3") (pintype "passive"))
    )
    (net (code "89") (name "VCC_12V") (class "Default")
      (node (ref "P10") (pin "1") (pinfunction "1_1") (pintype "passive"))
      (node (ref "P10") (pin "2") (pinfunction "2_2") (pintype "passive"))
      (node (ref "P10") (pin "3") (pinfunction "3_3") (pintype "passive"))
      (node (ref "P10") (pin "4") (pinfunction "4_4") (pintype "passive"))
    )
    (net (code "90") (name "unconnected-(IC2-R1IN-Pad13)") (class "Default")
      (node (ref "IC2") (pin "13") (pinfunction "R1IN_13") (pintype "passive+no_connect"))
    )
    (net (code "91") (name "unconnected-(IC2-R1OUT-Pad12)") (class "Default")
      (node (ref "IC2") (pin "12") (pinfunction "R1OUT_12") (pintype "passive+no_connect"))
    )
    (net (code "92") (name "unconnected-(IC2-T1IN-Pad11)") (class "Default")
      (node (ref "IC2") (pin "11") (pinfunction "T1IN_11") (pintype "passive+no_connect"))
    )
    (net (code "93") (name "unconnected-(IC2-T1OUT-Pad14)") (class "Default")
      (node (ref "IC2") (pin "14") (pinfunction "T1OUT_14") (pintype "passive+no_connect"))
    )
    (net (code "94") (name "unconnected-(IC3-RXER{slash}~{PHYAD0}-Pad10)") (class "Default")
      (node (ref "IC3") (pin "10") (pinfunction "RXER/~{PHYAD0}_10") (pintype "passive+no_connect"))
    )
    (net (code "95") (name "unconnected-(IC3-VDDCR-Pad6)") (class "Default")
      (node (ref "IC3") (pin "6") (pinfunction "VDDCR_6") (pintype "passive+no_connect"))
    )
    (net (code "96") (name "unconnected-(J1-Pad1)") (class "Default")
      (node (ref "J1") (pin "1") (pinfunction "1_1") (pintype "passive+no_connect"))
    )
    (net (code "97") (name "unconnected-(J1-Pad4)") (class "Default")
      (node (ref "J1") (pin "4") (pinfunction "4_4") (pintype "passive+no_connect"))
    )
    (net (code "98") (name "unconnected-(J1-Pad6)") (class "Default")
      (node (ref "J1") (pin "6") (pinfunction "6_6") (pintype "passive+no_connect"))
    )
    (net (code "99") (name "unconnected-(J1-Pad7)") (class "Default")
      (node (ref "J1") (pin "7") (pinfunction "7_7") (pintype "passive+no_connect"))
    )
    (net (code "100") (name "unconnected-(J1-Pad8)") (class "Default")
      (node (ref "J1") (pin "8") (pinfunction "8_8") (pintype "passive+no_connect"))
    )
    (net (code "101") (name "unconnected-(J1-Pad9)") (class "Default")
      (node (ref "J1") (pin "9") (pinfunction "9_9") (pintype "passive+no_connect"))
    )
    (net (code "102") (name "unconnected-(P9-ID-Pad4)") (class "Default")
      (node (ref "P9") (pin "4") (pinfunction "ID_4") (pintype "passive+no_connect"))
    )
    (net (code "103") (name "unconnected-(RJ2-NC-Pad7)") (class "Default")
      (node (ref "RJ2") (pin "7") (pinfunction "NC_7") (pintype "passive"))
    )
    (net (code "104") (name "unconnected-(RJ2-NC-Pad8)") (class "Default")
      (node (ref "RJ2") (pin "8") (pinfunction "NC_8") (pintype "passive"))
    )
    (net (code "105") (name "unconnected-(RJ2-RCT-Pad5)") (class "Default")
      (node (ref "RJ2") (pin "5") (pinfunction "RCT_5") (pintype "passive"))
    )
    (net (code "106") (name "unconnected-(RJ2-RD+-Pad3)") (class "Default")
      (node (ref "RJ2") (pin "3") (pinfunction "RD+_3") (pintype "passive"))
    )
    (net (code "107") (name "unconnected-(RJ2-RD--Pad6)") (class "Default")
      (node (ref "RJ2") (pin "6") (pinfunction "RD-_6") (pintype "passive"))
    )
    (net (code "108") (name "unconnected-(RJ2-TCT-Pad4)") (class "Default")
      (node (ref "RJ2") (pin "4") (pinfunction "TCT_4") (pintype "passive"))
    )
    (net (code "109") (name "unconnected-(RJ3-NC-Pad7)") (class "Default")
      (node (ref "RJ3") (pin "7") (pinfunction "NC_7") (pintype "passive"))
    )
    (net (code "110") (name "unconnected-(RJ3-NC-Pad8)") (class "Default")
      (node (ref "RJ3") (pin "8") (pinfunction "NC_8") (pintype "passive"))
    )
    (net (code "111") (name "unconnected-(RJ3-RCT-Pad5)") (class "Default")
      (node (ref "RJ3") (pin "5") (pinfunction "RCT_5") (pintype "passive"))
    )
    (net (code "112") (name "unconnected-(RJ3-RD+-Pad3)") (class "Default")
      (node (ref "RJ3") (pin "3") (pinfunction "RD+_3") (pintype "passive"))
    )
    (net (code "113") (name "unconnected-(RJ3-RD--Pad6)") (class "Default")
      (node (ref "RJ3") (pin "6") (pinfunction "RD-_6") (pintype "passive"))
    )
    (net (code "114") (name "unconnected-(RJ3-TCT-Pad4)") (class "Default")
      (node (ref "RJ3") (pin "4") (pinfunction "TCT_4") (pintype "passive"))
    )
    (net (code "115") (name "unconnected-(U2-D0-Pad2)") (class "Default")
      (node (ref "U2") (pin "2") (pinfunction "D0_2") (pintype "passive+no_connect"))
    )
    (net (code "116") (name "unconnected-(U2-D1-Pad3)") (class "Default")
      (node (ref "U2") (pin "3") (pinfunction "D1_3") (pintype "passive+no_connect"))
    )
    (net (code "117") (name "unconnected-(U2-D2-Pad4)") (class "Default")
      (node (ref "U2") (pin "4") (pinfunction "D2_4") (pintype "passive+no_connect"))
    )
    (net (code "118") (name "unconnected-(U2-D3-Pad5)") (class "Default")
      (node (ref "U2") (pin "5") (pinfunction "D3_5") (pintype "passive+no_connect"))
    )
    (net (code "119") (name "unconnected-(U2-D4-Pad6)") (class "Default")
      (node (ref "U2") (pin "6") (pinfunction "D4_6") (pintype "passive+no_connect"))
    )
    (net (code "120") (name "unconnected-(U2-D5-Pad7)") (class "Default")
      (node (ref "U2") (pin "7") (pinfunction "D5_7") (pintype "passive+no_connect"))
    )
    (net (code "121") (name "unconnected-(U2-RX-Pad13)") (class "Default")
      (node (ref "U2") (pin "13") (pinfunction "RX_13") (pintype "passive+no_connect"))
    )
    (net (code "122") (name "unconnected-(U2-SWCLK-Pad9)") (class "Default")
      (node (ref "U2") (pin "9") (pinfunction "SWCLK_9") (pintype "passive+no_connect"))
    )
    (net (code "123") (name "unconnected-(U2-SWDIO-Pad10)") (class "Default")
      (node (ref "U2") (pin "10") (pinfunction "SWDIO_10") (pintype "passive+no_connect"))
    )
    (net (code "124") (name "unconnected-(U2-TX-Pad14)") (class "Default")
      (node (ref "U2") (pin "14") (pinfunction "TX_14") (pintype "passive+no_connect"))
    )
    (net (code "125") (name "unconnected-(U3-Vref-Pad5)") (class "Default")
      (node (ref "U3") (pin "5") (pinfunction "Vref_5") (pintype "passive+no_connect"))
    )
    (net (code "126") (name "unconnected-(U4-Vref-Pad5)") (class "Default")
      (node (ref "U4") (pin "5") (pinfunction "Vref_5") (pintype "passive+no_connect"))
    )
  )
)
